# DC_POWER_Block.net
KiCad netlist of a schematic drawn in Altium Designer
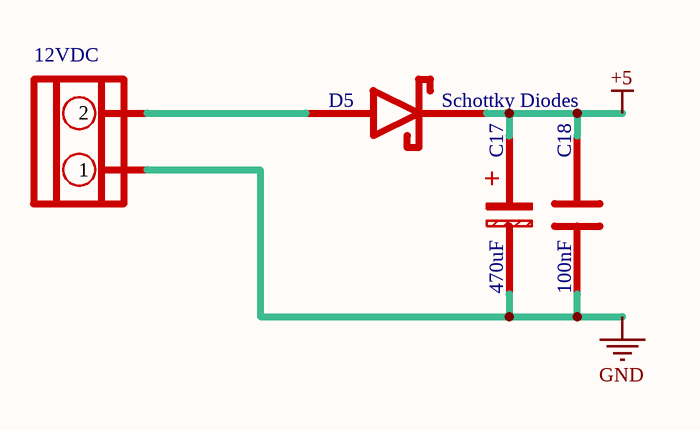
[diagram p0: DC_POWER_Block.SchDoc]

(export (version "E")
  (design (tool "Eeschema 10.0.6"))
  (components
    (comp (ref "C17")
      (value "470uF")
      (footprint "CAP-AL-4x5.4")
      (description "Aluminum Capacitor")
      (libsource (lib "CTAI-Library") (part "CAP-ALU"))
    )
    (comp (ref "C18")
      (value "100nF")
      (footprint "C0805")
      (description "Ceramic Capacitor")
      (libsource (lib "CTAI-Library") (part "CAP-CER"))
    )
    (comp (ref "D5")
      (value "Schottky Diodes")
      (footprint "SMA")
      (description "Schottky diodes")
      (libsource (lib "CTAI-Library") (part "Diode_Schottky"))
    )
    (comp (ref "H3")
      (value "12VDC")
      (footprint "KF301-2-V")
      (description "Connector 5.08MM Pitch Vertical 2 Pole")
      (libsource (lib "CTAI-Library") (part "KF301-2-V"))
    )
  )
  (nets
    (net (code "1") (name "+5") (class "Default")
      (node (ref "C17") (pin "1") (pintype "passive"))
      (node (ref "C18") (pin "2") (pintype "passive"))
      (node (ref "D5") (pin "K") (pinfunction "K_K") (pintype "passive"))
    )
    (net (code "2") (name "GND") (class "Default")
      (node (ref "C17") (pin "2") (pintype "passive"))
      (node (ref "C18") (pin "1") (pintype "passive"))
      (node (ref "H3") (pin "1") (pinfunction "1_1") (pintype "passive"))
    )
    (net (code "3") (name "Net-(D5-PadA)") (class "Default")
      (node (ref "D5") (pin "A") (pinfunction "A_A") (pintype "passive"))
      (node (ref "H3") (pin "2") (pinfunction "2_2") (pintype "passive"))
    )
  )
)
